# main_board.net
KiCad netlist of a schematic drawn in EAGLE
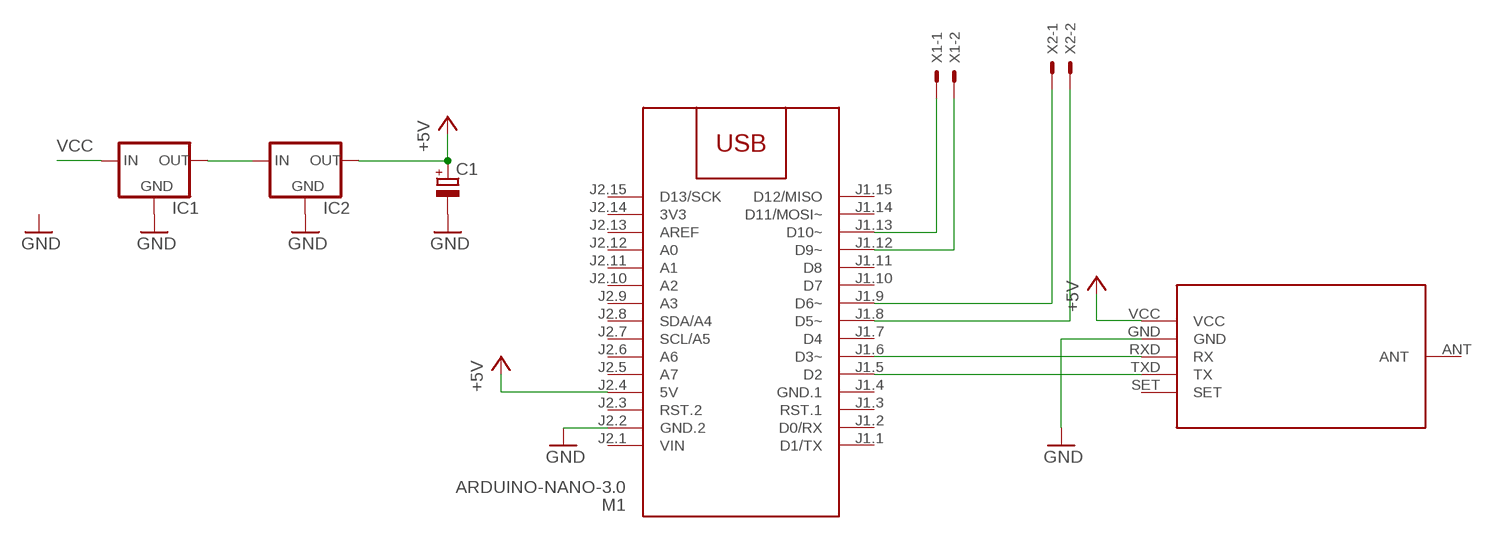
[diagram p0: schematic, sheet 1]

(export (version "E")
  (design (tool "Eeschema 10.0.6"))
  (components
    (comp (ref "C1")
      (value "CPOL-EUE2.5-7")
      (footprint "eagle-import:E2,5-7")
      (libsource (lib "eagle-import") (part "CPOL-EUE2.5-7"))
    )
    (comp (ref "IC1")
      (value "78XXS")
      (footprint "eagle-import:78XXS")
      (libsource (lib "eagle-import") (part "78XXS"))
    )
    (comp (ref "IC2")
      (value "78XXS")
      (footprint "eagle-import:78XXS")
      (libsource (lib "eagle-import") (part "78XXS"))
    )
    (comp (ref "M1")
      (value "ARDUINO-NANO-3.0")
      (footprint "eagle-import:ARDUINO-NANO-3.0")
      (libsource (lib "eagle-import") (part "ARDUINO-NANO-3.0"))
    )
    (comp (ref "U$1")
      (value "HC-12_FOOTPRINT")
      (footprint "eagle-import:HC-12_FOOTPRINT")
      (libsource (lib "eagle-import") (part "HC-12_FOOTPRINT"))
    )
    (comp (ref "X1")
      (value "22-23-2021")
      (footprint "eagle-import:22-23-2021")
      (fields (field (name "MF") "MOLEX"))
      (libsource (lib "eagle-import") (part "22-23-2021"))
    )
    (comp (ref "X2")
      (value "22-23-2021")
      (footprint "eagle-import:22-23-2021")
      (fields (field (name "MF") "MOLEX"))
      (libsource (lib "eagle-import") (part "22-23-2021"))
    )
  )
  (nets
    (net (code "1") (name "+5V") (class "Default")
      (node (ref "C1") (pin "+") (pinfunction "+_+") (pintype "passive"))
      (node (ref "IC2") (pin "OUT") (pinfunction "OUT_OUT") (pintype "passive"))
      (node (ref "M1") (pin "J2.4") (pinfunction "5V_J2.4") (pintype "power_in"))
      (node (ref "U$1") (pin "VCC") (pinfunction "VCC_VCC") (pintype "bidirectional"))
    )
    (net (code "2") (name "/3V3") (class "Default")
      (node (ref "M1") (pin "J2.14") (pinfunction "3V3_J2.14") (pintype "power_in"))
    )
    (net (code "3") (name "/GND.1") (class "Default")
      (node (ref "M1") (pin "J1.4") (pinfunction "GND.1_J1.4") (pintype "power_in"))
    )
    (net (code "4") (name "/VCC") (class "Default")
      (node (ref "IC1") (pin "IN") (pinfunction "IN_IN") (pintype "input"))
    )
    (net (code "5") (name "/VIN") (class "Default")
      (node (ref "M1") (pin "J2.1") (pinfunction "VIN_J2.1") (pintype "power_in"))
    )
    (net (code "6") (name "GND") (class "Default")
      (node (ref "C1") (pin "-") (pinfunction "-_-") (pintype "passive"))
      (node (ref "IC1") (pin "GND") (pinfunction "GND_GND") (pintype "input"))
      (node (ref "IC2") (pin "GND") (pinfunction "GND_GND") (pintype "input"))
      (node (ref "M1") (pin "J2.2") (pinfunction "GND.2_J2.2") (pintype "power_in"))
      (node (ref "U$1") (pin "GND") (pinfunction "GND_GND") (pintype "bidirectional"))
    )
    (net (code "7") (name "Net-(IC1-PadOUT)") (class "Default")
      (node (ref "IC1") (pin "OUT") (pinfunction "OUT_OUT") (pintype "passive"))
      (node (ref "IC2") (pin "IN") (pinfunction "IN_IN") (pintype "input"))
    )
    (net (code "8") (name "Net-(M1-D2)") (class "Default")
      (node (ref "M1") (pin "J1.5") (pinfunction "D2_J1.5") (pintype "bidirectional"))
      (node (ref "U$1") (pin "TXD") (pinfunction "TX_TXD") (pintype "bidirectional"))
    )
    (net (code "9") (name "Net-(M1-D3~{})") (class "Default")
      (node (ref "M1") (pin "J1.6") (pinfunction "D3~{}_J1.6") (pintype "bidirectional"))
      (node (ref "U$1") (pin "RXD") (pinfunction "RX_RXD") (pintype "bidirectional"))
    )
    (net (code "10") (name "Net-(M1-D5~{})") (class "Default")
      (node (ref "M1") (pin "J1.8") (pinfunction "D5~{}_J1.8") (pintype "bidirectional"))
      (node (ref "X2") (pin "2") (pinfunction "S_2") (pintype "passive"))
    )
    (net (code "11") (name "Net-(M1-D6~{})") (class "Default")
      (node (ref "M1") (pin "J1.9") (pinfunction "D6~{}_J1.9") (pintype "bidirectional"))
      (node (ref "X2") (pin "1") (pinfunction "S_1") (pintype "passive"))
    )
    (net (code "12") (name "Net-(M1-D9~{})") (class "Default")
      (node (ref "M1") (pin "J1.12") (pinfunction "D9~{}_J1.12") (pintype "bidirectional"))
      (node (ref "X1") (pin "2") (pinfunction "S_2") (pintype "passive"))
    )
    (net (code "13") (name "Net-(M1-D10~{})") (class "Default")
      (node (ref "M1") (pin "J1.13") (pinfunction "D10~{}_J1.13") (pintype "bidirectional"))
      (node (ref "X1") (pin "1") (pinfunction "S_1") (pintype "passive"))
    )
    (net (code "14") (name "unconnected-(M1-A0-PadJ2.12)") (class "Default")
      (node (ref "M1") (pin "J2.12") (pinfunction "A0_J2.12") (pintype "bidirectional"))
    )
    (net (code "15") (name "unconnected-(M1-A1-PadJ2.11)") (class "Default")
      (node (ref "M1") (pin "J2.11") (pinfunction "A1_J2.11") (pintype "bidirectional"))
    )
    (net (code "16") (name "unconnected-(M1-A2-PadJ2.10)") (class "Default")
      (node (ref "M1") (pin "J2.10") (pinfunction "A2_J2.10") (pintype "bidirectional"))
    )
    (net (code "17") (name "unconnected-(M1-A3-PadJ2.9)") (class "Default")
      (node (ref "M1") (pin "J2.9") (pinfunction "A3_J2.9") (pintype "bidirectional"))
    )
    (net (code "18") (name "unconnected-(M1-A6-PadJ2.6)") (class "Default")
      (node (ref "M1") (pin "J2.6") (pinfunction "A6_J2.6") (pintype "bidirectional"))
    )
    (net (code "19") (name "unconnected-(M1-A7-PadJ2.5)") (class "Default")
      (node (ref "M1") (pin "J2.5") (pinfunction "A7_J2.5") (pintype "bidirectional"))
    )
    (net (code "20") (name "unconnected-(M1-AREF-PadJ2.13)") (class "Default")
      (node (ref "M1") (pin "J2.13") (pinfunction "AREF_J2.13") (pintype "bidirectional"))
    )
    (net (code "21") (name "unconnected-(M1-D0{slash}RX-PadJ1.2)") (class "Default")
      (node (ref "M1") (pin "J1.2") (pinfunction "D0/RX_J1.2") (pintype "bidirectional"))
    )
    (net (code "22") (name "unconnected-(M1-D1{slash}TX-PadJ1.1)") (class "Default")
      (node (ref "M1") (pin "J1.1") (pinfunction "D1/TX_J1.1") (pintype "bidirectional"))
    )
    (net (code "23") (name "unconnected-(M1-D4-PadJ1.7)") (class "Default")
      (node (ref "M1") (pin "J1.7") (pinfunction "D4_J1.7") (pintype "bidirectional"))
    )
    (net (code "24") (name "unconnected-(M1-D7-PadJ1.10)") (class "Default")
      (node (ref "M1") (pin "J1.10") (pinfunction "D7_J1.10") (pintype "bidirectional"))
    )
    (net (code "25") (name "unconnected-(M1-D8-PadJ1.11)") (class "Default")
      (node (ref "M1") (pin "J1.11") (pinfunction "D8_J1.11") (pintype "bidirectional"))
    )
    (net (code "26") (name "unconnected-(M1-D11{slash}MOSI~{}-PadJ1.14)") (class "Default")
      (node (ref "M1") (pin "J1.14") (pinfunction "D11/MOSI~{}_J1.14") (pintype "bidirectional"))
    )
    (net (code "27") (name "unconnected-(M1-D12{slash}MISO-PadJ1.15)") (class "Default")
      (node (ref "M1") (pin "J1.15") (pinfunction "D12/MISO_J1.15") (pintype "bidirectional"))
    )
    (net (code "28") (name "unconnected-(M1-D13{slash}SCK-PadJ2.15)") (class "Default")
      (node (ref "M1") (pin "J2.15") (pinfunction "D13/SCK_J2.15") (pintype "bidirectional"))
    )
    (net (code "29") (name "unconnected-(M1-RST.1-PadJ1.3)") (class "Default")
      (node (ref "M1") (pin "J1.3") (pinfunction "RST.1_J1.3") (pintype "bidirectional"))
    )
    (net (code "30") (name "unconnected-(M1-RST.2-PadJ2.3)") (class "Default")
      (node (ref "M1") (pin "J2.3") (pinfunction "RST.2_J2.3") (pintype "bidirectional"))
    )
    (net (code "31") (name "unconnected-(M1-SCL{slash}A5-PadJ2.7)") (class "Default")
      (node (ref "M1") (pin "J2.7") (pinfunction "SCL/A5_J2.7") (pintype "bidirectional"))
    )
    (net (code "32") (name "unconnected-(M1-SDA{slash}A4-PadJ2.8)") (class "Default")
      (node (ref "M1") (pin "J2.8") (pinfunction "SDA/A4_J2.8") (pintype "bidirectional"))
    )
    (net (code "33") (name "unconnected-(U$1-PadANT)") (class "Default")
      (node (ref "U$1") (pin "ANT") (pinfunction "ANT_ANT") (pintype "bidirectional"))
    )
    (net (code "34") (name "unconnected-(U$1-PadSET)") (class "Default")
      (node (ref "U$1") (pin "SET") (pinfunction "SET_SET") (pintype "bidirectional"))
    )
  )
)
